# ECOGr2.net
KiCad netlist of a schematic drawn in Altium Designer
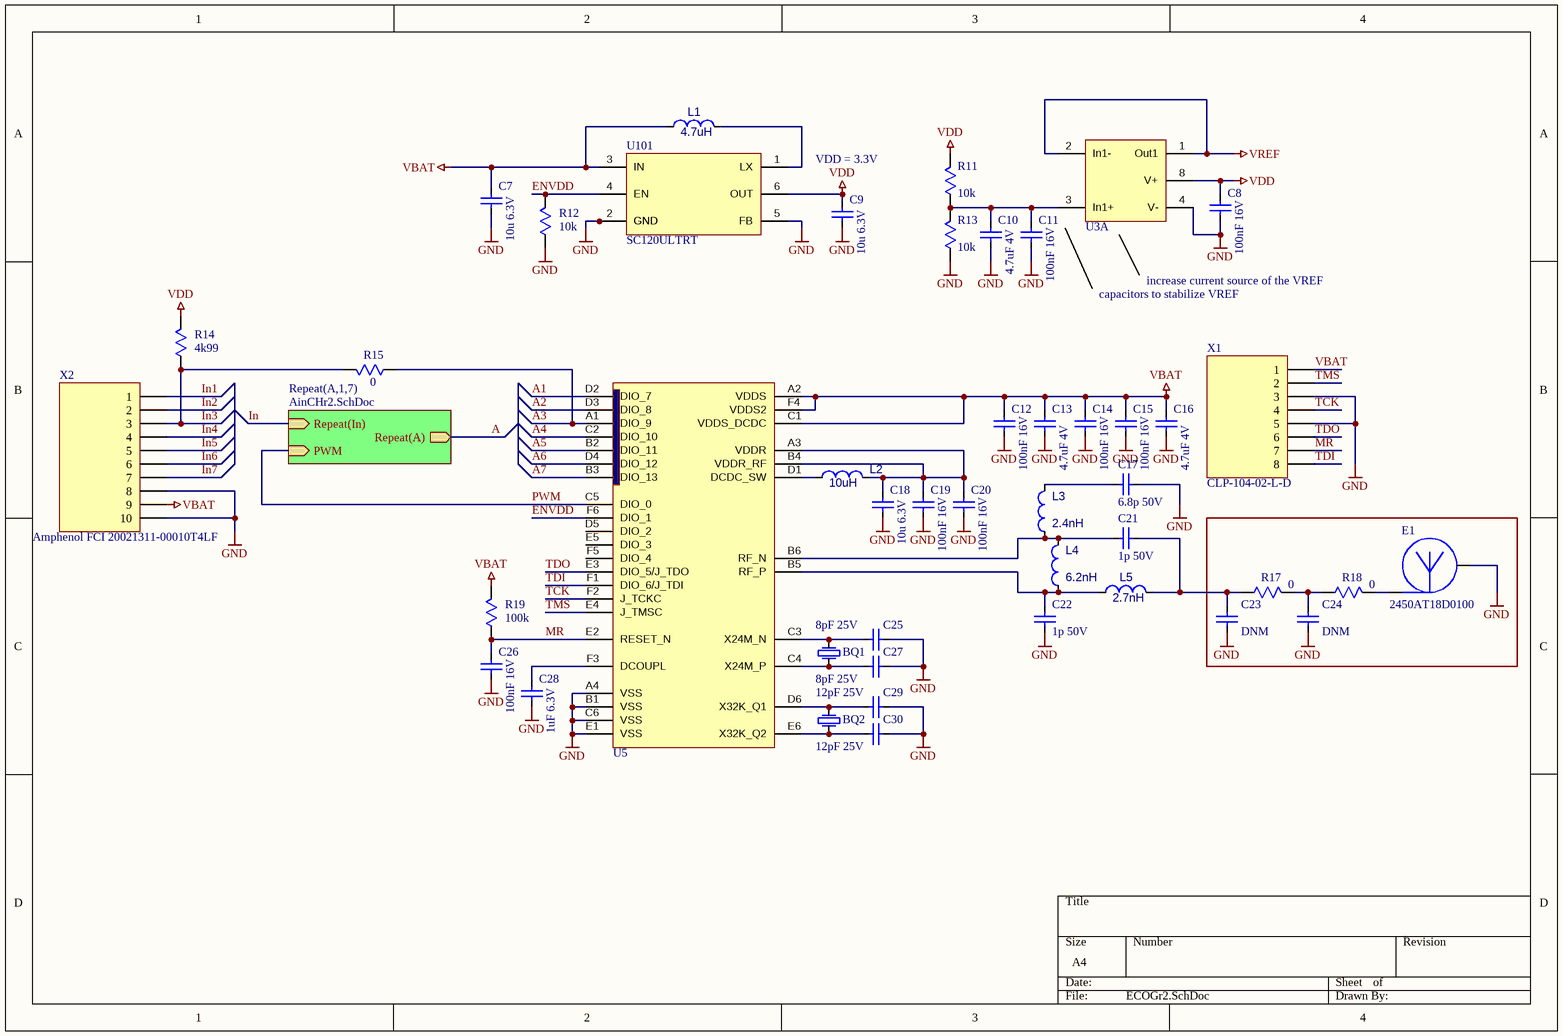
[diagram p0: ECOGr2.SchDoc]

(export (version "E")
  (design (tool "Eeschema 10.0.6"))
  (components
    (comp (ref "BQ1")
      (value "KX-4 24MHz")
      (footprint "KX–4")
      (description "SURFACE MOUNT CRYSTAL")
      (libsource (lib "ECOG") (part "KX series"))
    )
    (comp (ref "BQ2")
      (value "KX-327")
      (footprint "KX–327VT")
      (description "SURFACE MOUNT CRYSTAL")
      (libsource (lib "ECOG") (part "KX-327"))
    )
    (comp (ref "C7")
      (value "10u 6.3V")
      (footprint "CAPC1005L")
      (description "Capacitor")
      (libsource (lib "ECOG") (part "Capacitor"))
    )
    (comp (ref "C8")
      (value "100nF 16V")
      (footprint "CAPC0603L")
      (description "Capacitor")
      (libsource (lib "ECOG") (part "Capacitor"))
    )
    (comp (ref "C9")
      (value "10u 6.3V")
      (footprint "CAPC1005L")
      (description "Capacitor")
      (libsource (lib "ECOG") (part "Capacitor"))
    )
    (comp (ref "C10")
      (value "4.7uF 4V")
      (footprint "CAPC0603L")
      (description "Capacitor")
      (libsource (lib "ECOG") (part "Capacitor"))
    )
    (comp (ref "C11")
      (value "100nF 16V")
      (footprint "CAPC0603L")
      (description "Capacitor")
      (libsource (lib "ECOG") (part "Capacitor"))
    )
    (comp (ref "C12")
      (value "100nF 16V")
      (footprint "CAPC0603L")
      (description "Capacitor")
      (libsource (lib "ECOG") (part "Capacitor"))
    )
    (comp (ref "C13")
      (value "4.7uF 4V")
      (footprint "CAPC0603L")
      (description "Capacitor")
      (libsource (lib "ECOG") (part "Capacitor"))
    )
    (comp (ref "C14")
      (value "100nF 16V")
      (footprint "CAPC0603L")
      (description "Capacitor")
      (libsource (lib "ECOG") (part "Capacitor"))
    )
    (comp (ref "C15")
      (value "100nF 16V")
      (footprint "CAPC0603L")
      (description "Capacitor")
      (libsource (lib "ECOG") (part "Capacitor"))
    )
    (comp (ref "C16")
      (value "4.7uF 4V")
      (footprint "CAPC0603L")
      (description "Capacitor")
      (libsource (lib "ECOG") (part "Capacitor"))
    )
    (comp (ref "C17")
      (value "6.8p 50V")
      (footprint "CAPC0603L")
      (description "Capacitor")
      (libsource (lib "ECOG") (part "Capacitor"))
    )
    (comp (ref "C18")
      (value "10u 6.3V")
      (footprint "CAPC1005L")
      (description "Capacitor")
      (libsource (lib "ECOG") (part "Capacitor"))
    )
    (comp (ref "C19")
      (value "100nF 16V")
      (footprint "CAPC0603L")
      (description "Capacitor")
      (libsource (lib "ECOG") (part "Capacitor"))
    )
    (comp (ref "C20")
      (value "100nF 16V")
      (footprint "CAPC0603L")
      (description "Capacitor")
      (libsource (lib "ECOG") (part "Capacitor"))
    )
    (comp (ref "C21")
      (value "1p 50V")
      (footprint "CAPC0603L")
      (description "Capacitor")
      (libsource (lib "ECOG") (part "Capacitor"))
    )
    (comp (ref "C22")
      (value "1p 50V")
      (footprint "CAPC0603L")
      (description "Capacitor")
      (libsource (lib "ECOG") (part "Capacitor"))
    )
    (comp (ref "C23")
      (value "DNM")
      (footprint "CAPC1005L")
      (description "Capacitor")
      (libsource (lib "ECOG") (part "Capacitor"))
    )
    (comp (ref "C24")
      (value "DNM")
      (footprint "CAPC1005L")
      (description "Capacitor")
      (libsource (lib "ECOG") (part "Capacitor"))
    )
    (comp (ref "C25")
      (value "8pF 25V")
      (footprint "CAPC0603L")
      (description "Capacitor")
      (libsource (lib "ECOG") (part "Capacitor"))
    )
    (comp (ref "C26")
      (value "100nF 16V")
      (footprint "CAPC0603L")
      (description "Capacitor")
      (libsource (lib "ECOG") (part "Capacitor"))
    )
    (comp (ref "C27")
      (value "8pF 25V")
      (footprint "CAPC0603L")
      (description "Capacitor")
      (libsource (lib "ECOG") (part "Capacitor"))
    )
    (comp (ref "C28")
      (value "1uF 6.3V")
      (footprint "CAPC0603L")
      (description "Capacitor")
      (libsource (lib "ECOG") (part "Capacitor"))
    )
    (comp (ref "C29")
      (value "12pF 25V")
      (footprint "CAPC0603L")
      (description "Capacitor")
      (libsource (lib "ECOG") (part "Capacitor"))
    )
    (comp (ref "C30")
      (value "12pF 25V")
      (footprint "CAPC0603L")
      (description "Capacitor")
      (libsource (lib "ECOG") (part "Capacitor"))
    )
    (comp (ref "E1")
      (value "2450AT18D0100")
      (footprint "2450AT18D0100")
      (description "Antenna")
      (libsource (lib "ECOG") (part "Antenna"))
    )
    (comp (ref "L1")
      (value "4.7uH")
      (footprint "INDC1608L")
      (description "Inductor")
      (libsource (lib "ECOG") (part "Inductor"))
    )
    (comp (ref "L2")
      (value "10uH")
      (footprint "INDC0603L")
      (description "Inductor")
      (libsource (lib "ECOG") (part "Inductor"))
    )
    (comp (ref "L3")
      (value "2.4nH")
      (footprint "INDC0603L")
      (description "Inductor")
      (libsource (lib "ECOG") (part "Inductor"))
    )
    (comp (ref "L4")
      (value "6.2nH")
      (footprint "INDC0603L")
      (description "Inductor")
      (libsource (lib "ECOG") (part "Inductor"))
    )
    (comp (ref "L5")
      (value "2.7nH")
      (footprint "INDC0603L")
      (description "Inductor")
      (libsource (lib "ECOG") (part "Inductor"))
    )
    (comp (ref "R11")
      (value "10k")
      (footprint "RESC0603L")
      (description "Resistor")
      (libsource (lib "ECOG") (part "Resistor"))
    )
    (comp (ref "R12")
      (value "10k")
      (footprint "RESC0603L")
      (description "Resistor")
      (libsource (lib "ECOG") (part "Resistor"))
    )
    (comp (ref "R13")
      (value "10k")
      (footprint "RESC0603L")
      (description "Resistor")
      (libsource (lib "ECOG") (part "Resistor"))
    )
    (comp (ref "R14")
      (value "4k99")
      (footprint "RESC0603L")
      (description "Resistor")
      (libsource (lib "ECOG") (part "Resistor"))
    )
    (comp (ref "R15")
      (value "0")
      (footprint "RESC0603L")
      (description "Resistor")
      (libsource (lib "ECOG") (part "Resistor"))
    )
    (comp (ref "R17")
      (value "0")
      (footprint "RESC1005L")
      (description "Resistor")
      (libsource (lib "ECOG") (part "Resistor"))
    )
    (comp (ref "R18")
      (value "0")
      (footprint "RESC1005L")
      (description "Resistor")
      (libsource (lib "ECOG") (part "Resistor"))
    )
    (comp (ref "R19")
      (value "100k")
      (footprint "RESC0603L")
      (description "Resistor")
      (libsource (lib "ECOG") (part "Resistor"))
    )
    (comp (ref "U3")
      (value "LMX358IQ2T")
      (footprint "SON50P200X60_HS-9L")
      (description "Operational Amplifier for Cost-Sensitive Systems")
      (libsource (lib "ECOG") (part "LMX358"))
    )
    (comp (ref "U5")
      (value "Bluetooth wireless MCU")
      (footprint "BGA34C40P6X6_268X268X57")
      (libsource (lib "ECOG") (part "CC2640R2FYFV"))
    )
    (comp (ref "U101")
      (value "SC120ULTRT")
      (footprint "SON50P150X60_HS-7L")
      (description "Step-up converter")
      (libsource (lib "ECOG") (part "SC120ULTRT"))
    )
    (comp (ref "X1")
      (value "CLP-104-02-L-D")
      (footprint "HDR-1.27mm-2X4-smd")
      (description "Header")
      (libsource (lib "ECOG") (part "DB-8F"))
    )
    (comp (ref "X2")
      (value "Amphenol FCI 20021311-00010T4LF")
      (footprint "HDR-1.27mm-2X5")
      (description "Header")
      (libsource (lib "ECOG") (part "DB-10F"))
    )
  )
  (nets
    (net (code "2") (name "/A1") (class "Default")
      (node (ref "U5") (pin "D2") (pinfunction "DIO_7_D2") (pintype "passive"))
    )
    (net (code "3") (name "/A2") (class "Default")
      (node (ref "U5") (pin "D3") (pinfunction "DIO_8_D3") (pintype "passive"))
    )
    (net (code "4") (name "/A3") (class "Default")
      (node (ref "R15") (pin "1") (pinfunction "1_1") (pintype "passive"))
      (node (ref "U5") (pin "A1") (pinfunction "DIO_9_A1") (pintype "passive"))
    )
    (net (code "5") (name "/A4") (class "Default")
      (node (ref "U5") (pin "C2") (pinfunction "DIO_10_C2") (pintype "passive"))
    )
    (net (code "6") (name "/A5") (class "Default")
      (node (ref "U5") (pin "B2") (pinfunction "DIO_11_B2") (pintype "passive"))
    )
    (net (code "7") (name "/A6") (class "Default")
      (node (ref "U5") (pin "D4") (pinfunction "DIO_12_D4") (pintype "passive"))
    )
    (net (code "8") (name "/A7") (class "Default")
      (node (ref "U5") (pin "B3") (pinfunction "DIO_13_B3") (pintype "passive"))
    )
    (net (code "9") (name "/ENVDD") (class "Default")
      (node (ref "R12") (pin "2") (pinfunction "2_2") (pintype "passive"))
      (node (ref "U101") (pin "4") (pinfunction "EN_4") (pintype "passive"))
      (node (ref "U5") (pin "F6") (pinfunction "DIO_1_F6") (pintype "passive"))
    )
    (net (code "11") (name "/In1") (class "Default")
      (node (ref "X2") (pin "1") (pinfunction "1_1") (pintype "passive"))
    )
    (net (code "12") (name "/In2") (class "Default")
      (node (ref "X2") (pin "2") (pinfunction "2_2") (pintype "passive"))
    )
    (net (code "13") (name "/In3") (class "Default")
      (node (ref "R14") (pin "1") (pinfunction "1_1") (pintype "passive"))
      (node (ref "R15") (pin "2") (pinfunction "2_2") (pintype "passive"))
      (node (ref "X2") (pin "3") (pinfunction "3_3") (pintype "passive"))
    )
    (net (code "14") (name "/In4") (class "Default")
      (node (ref "X2") (pin "4") (pinfunction "4_4") (pintype "passive"))
    )
    (net (code "15") (name "/In5") (class "Default")
      (node (ref "X2") (pin "5") (pinfunction "5_5") (pintype "passive"))
    )
    (net (code "16") (name "/In6") (class "Default")
      (node (ref "X2") (pin "6") (pinfunction "6_6") (pintype "passive"))
    )
    (net (code "17") (name "/In7") (class "Default")
      (node (ref "X2") (pin "7") (pinfunction "7_7") (pintype "passive"))
    )
    (net (code "18") (name "/MR") (class "Default")
      (node (ref "C26") (pin "1") (pinfunction "1_1") (pintype "passive"))
      (node (ref "R19") (pin "1") (pinfunction "1_1") (pintype "passive"))
      (node (ref "U5") (pin "E2") (pinfunction "RESET_N_E2") (pintype "passive"))
      (node (ref "X1") (pin "7") (pinfunction "7_7") (pintype "passive"))
    )
    (net (code "19") (name "/PWM") (class "Default")
      (node (ref "U5") (pin "C5") (pinfunction "DIO_0_C5") (pintype "passive"))
    )
    (net (code "20") (name "/TCK") (class "Default")
      (node (ref "U5") (pin "F2") (pinfunction "J_TCKC_F2") (pintype "passive"))
      (node (ref "X1") (pin "4") (pinfunction "4_4") (pintype "passive"))
    )
    (net (code "21") (name "/TDI") (class "Default")
      (node (ref "U5") (pin "F1") (pinfunction "DIO_6/J_TDI_F1") (pintype "passive"))
      (node (ref "X1") (pin "8") (pinfunction "8_8") (pintype "passive"))
    )
    (net (code "22") (name "/TDO") (class "Default")
      (node (ref "U5") (pin "E3") (pinfunction "DIO_5/J_TDO_E3") (pintype "passive"))
      (node (ref "X1") (pin "6") (pinfunction "6_6") (pintype "passive"))
    )
    (net (code "23") (name "/TMS") (class "Default")
      (node (ref "U5") (pin "E4") (pinfunction "J_TMSC_E4") (pintype "passive"))
      (node (ref "X1") (pin "2") (pinfunction "2_2") (pintype "passive"))
    )
    (net (code "24") (name "GND") (class "Default")
      (node (ref "BQ1") (pin "2") (pinfunction "GND_2") (pintype "power_in"))
      (node (ref "BQ1") (pin "4") (pinfunction "GND_4") (pintype "power_in"))
      (node (ref "C10") (pin "2") (pinfunction "2_2") (pintype "passive"))
      (node (ref "C11") (pin "2") (pinfunction "2_2") (pintype "passive"))
      (node (ref "C12") (pin "2") (pinfunction "2_2") (pintype "passive"))
      (node (ref "C13") (pin "2") (pinfunction "2_2") (pintype "passive"))
      (node (ref "C14") (pin "2") (pinfunction "2_2") (pintype "passive"))
      (node (ref "C15") (pin "2") (pinfunction "2_2") (pintype "passive"))
      (node (ref "C16") (pin "2") (pinfunction "2_2") (pintype "passive"))
      (node (ref "C17") (pin "2") (pinfunction "2_2") (pintype "passive"))
      (node (ref "C18") (pin "2") (pinfunction "2_2") (pintype "passive"))
      (node (ref "C19") (pin "2") (pinfunction "2_2") (pintype "passive"))
      (node (ref "C20") (pin "2") (pinfunction "2_2") (pintype "passive"))
      (node (ref "C22") (pin "2") (pinfunction "2_2") (pintype "passive"))
      (node (ref "C23") (pin "1") (pinfunction "1_1") (pintype "passive"))
      (node (ref "C24") (pin "1") (pinfunction "1_1") (pintype "passive"))
      (node (ref "C25") (pin "2") (pinfunction "2_2") (pintype "passive"))
      (node (ref "C26") (pin "2") (pinfunction "2_2") (pintype "passive"))
      (node (ref "C27") (pin "2") (pinfunction "2_2") (pintype "passive"))
      (node (ref "C28") (pin "2") (pinfunction "2_2") (pintype "passive"))
      (node (ref "C29") (pin "2") (pinfunction "2_2") (pintype "passive"))
      (node (ref "C30") (pin "2") (pinfunction "2_2") (pintype "passive"))
      (node (ref "C7") (pin "2") (pinfunction "2_2") (pintype "passive"))
      (node (ref "C8") (pin "2") (pinfunction "2_2") (pintype "passive"))
      (node (ref "C9") (pin "2") (pinfunction "2_2") (pintype "passive"))
      (node (ref "E1") (pin "2") (pinfunction "GND_2") (pintype "passive"))
      (node (ref "R12") (pin "1") (pinfunction "1_1") (pintype "passive"))
      (node (ref "R13") (pin "1") (pinfunction "1_1") (pintype "passive"))
      (node (ref "U101") (pin "2") (pinfunction "GND_2") (pintype "passive"))
      (node (ref "U101") (pin "5") (pinfunction "FB_5") (pintype "passive"))
      (node (ref "U101") (pin "7") (pinfunction "GND_7") (pintype "passive"))
      (node (ref "U3") (pin "4") (pinfunction "V-_4") (pintype "passive"))
      (node (ref "U5") (pin "A4") (pinfunction "VSS_A4") (pintype "passive"))
      (node (ref "U5") (pin "B1") (pinfunction "VSS_B1") (pintype "passive"))
      (node (ref "U5") (pin "C6") (pinfunction "VSS_C6") (pintype "passive"))
      (node (ref "U5") (pin "E1") (pinfunction "VSS_E1") (pintype "passive"))
      (node (ref "X1") (pin "3") (pinfunction "3_3") (pintype "passive"))
      (node (ref "X1") (pin "5") (pinfunction "5_5") (pintype "passive"))
      (node (ref "X2") (pin "10") (pinfunction "10_10") (pintype "passive"))
      (node (ref "X2") (pin "8") (pinfunction "8_8") (pintype "passive"))
    )
    (net (code "25") (name "Net-(BQ1-Q1)") (class "Default")
      (node (ref "BQ1") (pin "1") (pinfunction "Q1_1") (pintype "passive"))
      (node (ref "C27") (pin "1") (pinfunction "1_1") (pintype "passive"))
      (node (ref "U5") (pin "C4") (pinfunction "X24M_P_C4") (pintype "passive"))
    )
    (net (code "26") (name "Net-(BQ1-Q2)") (class "Default")
      (node (ref "BQ1") (pin "3") (pinfunction "Q2_3") (pintype "passive"))
      (node (ref "C25") (pin "1") (pinfunction "1_1") (pintype "passive"))
      (node (ref "U5") (pin "C3") (pinfunction "X24M_N_C3") (pintype "passive"))
    )
    (net (code "27") (name "Net-(BQ2-Q1)") (class "Default")
      (node (ref "BQ2") (pin "1") (pinfunction "Q1_1") (pintype "passive"))
      (node (ref "C30") (pin "1") (pinfunction "1_1") (pintype "passive"))
      (node (ref "U5") (pin "E6") (pinfunction "X32K_Q2_E6") (pintype "passive"))
    )
    (net (code "28") (name "Net-(BQ2-Q2)") (class "Default")
      (node (ref "BQ2") (pin "2") (pinfunction "Q2_2") (pintype "passive"))
      (node (ref "C29") (pin "1") (pinfunction "1_1") (pintype "passive"))
      (node (ref "U5") (pin "D6") (pinfunction "X32K_Q1_D6") (pintype "passive"))
    )
    (net (code "29") (name "Net-(C17-Pad1)") (class "Default")
      (node (ref "C17") (pin "1") (pinfunction "1_1") (pintype "passive"))
      (node (ref "L3") (pin "2") (pinfunction "2_2") (pintype "passive"))
    )
    (net (code "30") (name "Net-(C21-Pad2)") (class "Default")
      (node (ref "C21") (pin "2") (pinfunction "2_2") (pintype "passive"))
      (node (ref "C23") (pin "2") (pinfunction "2_2") (pintype "passive"))
      (node (ref "L5") (pin "2") (pinfunction "2_2") (pintype "passive"))
      (node (ref "R17") (pin "1") (pinfunction "1_1") (pintype "passive"))
    )
    (net (code "31") (name "Net-(C24-Pad2)") (class "Default")
      (node (ref "C24") (pin "2") (pinfunction "2_2") (pintype "passive"))
      (node (ref "R17") (pin "2") (pinfunction "2_2") (pintype "passive"))
      (node (ref "R18") (pin "1") (pinfunction "1_1") (pintype "passive"))
    )
    (net (code "32") (name "Net-(E1-ANT)") (class "Default")
      (node (ref "E1") (pin "1") (pinfunction "ANT_1") (pintype "passive"))
      (node (ref "R18") (pin "2") (pinfunction "2_2") (pintype "passive"))
    )
    (net (code "33") (name "Net-(U3A-In1+)") (class "Default")
      (node (ref "C10") (pin "1") (pinfunction "1_1") (pintype "passive"))
      (node (ref "C11") (pin "1") (pinfunction "1_1") (pintype "passive"))
      (node (ref "R11") (pin "1") (pinfunction "1_1") (pintype "passive"))
      (node (ref "R13") (pin "2") (pinfunction "2_2") (pintype "passive"))
      (node (ref "U3") (pin "3") (pinfunction "In1+_3") (pintype "passive"))
    )
    (net (code "34") (name "Net-(U5-DCDC_SW)") (class "Default")
      (node (ref "L2") (pin "1") (pinfunction "1_1") (pintype "passive"))
      (node (ref "U5") (pin "D1") (pinfunction "DCDC_SW_D1") (pintype "passive"))
    )
    (net (code "35") (name "Net-(U5-DCOUPL)") (class "Default")
      (node (ref "C28") (pin "1") (pinfunction "1_1") (pintype "passive"))
      (node (ref "U5") (pin "F3") (pinfunction "DCOUPL_F3") (pintype "passive"))
    )
    (net (code "36") (name "Net-(U5-RF_N)") (class "Default")
      (node (ref "C21") (pin "1") (pinfunction "1_1") (pintype "passive"))
      (node (ref "L3") (pin "1") (pinfunction "1_1") (pintype "passive"))
      (node (ref "L4") (pin "2") (pinfunction "2_2") (pintype "passive"))
      (node (ref "U5") (pin "B6") (pinfunction "RF_N_B6") (pintype "passive"))
    )
    (net (code "37") (name "Net-(U5-RF_P)") (class "Default")
      (node (ref "C22") (pin "1") (pinfunction "1_1") (pintype "passive"))
      (node (ref "L4") (pin "1") (pinfunction "1_1") (pintype "passive"))
      (node (ref "L5") (pin "1") (pinfunction "1_1") (pintype "passive"))
      (node (ref "U5") (pin "B5") (pinfunction "RF_P_B5") (pintype "passive"))
    )
    (net (code "38") (name "Net-(U5-VDDR)") (class "Default")
      (node (ref "C18") (pin "1") (pinfunction "1_1") (pintype "passive"))
      (node (ref "C19") (pin "1") (pinfunction "1_1") (pintype "passive"))
      (node (ref "C20") (pin "1") (pinfunction "1_1") (pintype "passive"))
      (node (ref "L2") (pin "2") (pinfunction "2_2") (pintype "passive"))
      (node (ref "U5") (pin "A3") (pinfunction "VDDR_A3") (pintype "passive"))
      (node (ref "U5") (pin "B4") (pinfunction "VDDR_RF_B4") (pintype "passive"))
    )
    (net (code "39") (name "Net-(U101-LX)") (class "Default")
      (node (ref "L1") (pin "2") (pinfunction "2_2") (pintype "passive"))
      (node (ref "U101") (pin "1") (pinfunction "LX_1") (pintype "passive"))
    )
    (net (code "40") (name "VBAT") (class "Default")
      (node (ref "C12") (pin "1") (pinfunction "1_1") (pintype "passive"))
      (node (ref "C13") (pin "1") (pinfunction "1_1") (pintype "passive"))
      (node (ref "C14") (pin "1") (pinfunction "1_1") (pintype "passive"))
      (node (ref "C15") (pin "1") (pinfunction "1_1") (pintype "passive"))
      (node (ref "C16") (pin "1") (pinfunction "1_1") (pintype "passive"))
      (node (ref "C7") (pin "1") (pinfunction "1_1") (pintype "passive"))
      (node (ref "L1") (pin "1") (pinfunction "1_1") (pintype "passive"))
      (node (ref "R19") (pin "2") (pinfunction "2_2") (pintype "passive"))
      (node (ref "U101") (pin "3") (pinfunction "IN_3") (pintype "passive"))
      (node (ref "U5") (pin "A2") (pinfunction "VDDS_A2") (pintype "passive"))
      (node (ref "U5") (pin "C1") (pinfunction "VDDS_DCDC_C1") (pintype "passive"))
      (node (ref "U5") (pin "F4") (pinfunction "VDDS2_F4") (pintype "passive"))
      (node (ref "X1") (pin "1") (pinfunction "1_1") (pintype "passive"))
      (node (ref "X2") (pin "9") (pinfunction "9_9") (pintype "passive"))
    )
    (net (code "41") (name "VDD") (class "Default")
      (node (ref "C8") (pin "1") (pinfunction "1_1") (pintype "passive"))
      (node (ref "C9") (pin "1") (pinfunction "1_1") (pintype "passive"))
      (node (ref "R11") (pin "2") (pinfunction "2_2") (pintype "passive"))
      (node (ref "R14") (pin "2") (pinfunction "2_2") (pintype "passive"))
      (node (ref "U101") (pin "6") (pinfunction "OUT_6") (pintype "passive"))
      (node (ref "U3") (pin "8") (pinfunction "V+_8") (pintype "passive"))
    )
    (net (code "42") (name "VREF") (class "Default")
      (node (ref "U3") (pin "1") (pinfunction "Out1_1") (pintype "passive"))
      (node (ref "U3") (pin "2") (pinfunction "In1-_2") (pintype "passive"))
    )
    (net (code "43") (name "unconnected-(U5-DIO_2-PadD5)") (class "Default")
      (node (ref "U5") (pin "D5") (pinfunction "DIO_2_D5") (pintype "passive"))
    )
    (net (code "44") (name "unconnected-(U5-DIO_3-PadE5)") (class "Default")
      (node (ref "U5") (pin "E5") (pinfunction "DIO_3_E5") (pintype "passive"))
    )
    (net (code "45") (name "unconnected-(U5-DIO_4-PadF5)") (class "Default")
      (node (ref "U5") (pin "F5") (pinfunction "DIO_4_F5") (pintype "passive"))
    )
  )
)
